# MCU_STM32.net
KiCad netlist of a schematic drawn in Altium Designer
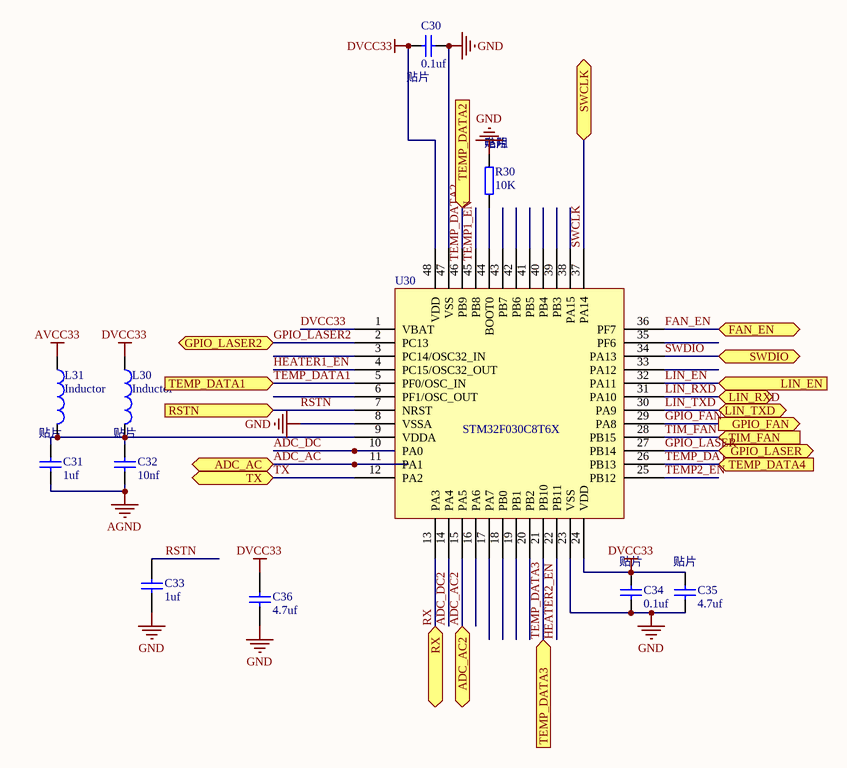
[diagram p0: MCU_STM32.SchDoc]

(export (version "E")
  (design (tool "Eeschema 10.0.6"))
  (components
    (comp (ref "C30")
      (value "0.1uf")
      (footprint "C0402")
      (description "Capacitor (Semiconductor SIM Model)")
      (libsource (lib "Miscellaneous Devices") (part "Cap Semi"))
    )
    (comp (ref "C31")
      (value "1uf")
      (footprint "C0402")
      (description "Capacitor (Semiconductor SIM Model)")
      (libsource (lib "Miscellaneous Devices") (part "Cap Semi"))
    )
    (comp (ref "C32")
      (value "10nf")
      (footprint "C0402")
      (description "Capacitor (Semiconductor SIM Model)")
      (libsource (lib "Miscellaneous Devices") (part "Cap Semi"))
    )
    (comp (ref "C33")
      (value "1uf")
      (footprint "C0402")
      (description "Capacitor 0402")
      (fields (field (name "PUBLISHER") "Altium Limited"))
      (libsource (lib "Capacitors") (part "C0402"))
    )
    (comp (ref "C34")
      (value "0.1uf")
      (footprint "C0402")
      (description "Capacitor (Semiconductor SIM Model)")
      (libsource (lib "Miscellaneous Devices") (part "Cap Semi"))
    )
    (comp (ref "C35")
      (value "4.7uf")
      (footprint "C0402")
      (description "Capacitor (Semiconductor SIM Model)")
      (libsource (lib "Miscellaneous Devices") (part "Cap Semi"))
    )
    (comp (ref "C36")
      (value "4.7uf")
      (footprint "C0402")
      (description "Capacitor 0402")
      (fields (field (name "PUBLISHER") "Altium Limited"))
      (libsource (lib "Capacitors") (part "C0402"))
    )
    (comp (ref "L30")
      (value "Inductor")
      (footprint "L0402")
      (fields (field (name "PUBLISHER") "Altium Limited"))
      (libsource (lib "Miscellaneous Devices") (part "Inductor"))
    )
    (comp (ref "L31")
      (value "Inductor")
      (footprint "L0402")
      (fields (field (name "PUBLISHER") "Altium Limited"))
      (libsource (lib "Miscellaneous Devices") (part "Inductor"))
    )
    (comp (ref "R30") (value "10K") (footprint "R0402") (libsource (lib "CxyDXP_SCH") (part "RES1")))
    (comp (ref "U30")
      (value "STM32F030C8T6X")
      (footprint "LQFP48S")
      (libsource (lib "STM32") (part "STM32F030C8T6X"))
    )
  )
  (nets
    (net (code "1") (name "/ADC_AC") (class "Default")
      (node (ref "U30") (pin "11") (pinfunction "PA1_11") (pintype "passive"))
    )
    (net (code "2") (name "/ADC_AC2") (class "Default")
      (node (ref "U30") (pin "15") (pinfunction "PA5_15") (pintype "passive"))
    )
    (net (code "3") (name "/ADC_DC") (class "Default")
      (node (ref "U30") (pin "10") (pinfunction "PA0_10") (pintype "passive"))
    )
    (net (code "4") (name "/ADC_DC2") (class "Default")
      (node (ref "U30") (pin "14") (pinfunction "PA4_14") (pintype "passive"))
    )
    (net (code "5") (name "/FAN_EN") (class "Default")
      (node (ref "U30") (pin "36") (pinfunction "PF7_36") (pintype "passive"))
    )
    (net (code "6") (name "/GPIO_FAN") (class "Default")
      (node (ref "U30") (pin "29") (pinfunction "PA8_29") (pintype "passive"))
    )
    (net (code "7") (name "/GPIO_LASER") (class "Default")
      (node (ref "U30") (pin "27") (pinfunction "PB14_27") (pintype "passive"))
    )
    (net (code "8") (name "/GPIO_LASER2") (class "Default")
      (node (ref "U30") (pin "2") (pinfunction "PC13_2") (pintype "passive"))
    )
    (net (code "9") (name "/HEATER1_EN") (class "Default")
      (node (ref "U30") (pin "4") (pinfunction "PC15/OSC32_OUT_4") (pintype "passive"))
    )
    (net (code "10") (name "/HEATER2_EN") (class "Default")
      (node (ref "U30") (pin "22") (pinfunction "PB11_22") (pintype "passive"))
    )
    (net (code "11") (name "/LIN_EN") (class "Default")
      (node (ref "U30") (pin "32") (pinfunction "PA11_32") (pintype "passive"))
    )
    (net (code "12") (name "/LIN_RXD") (class "Default")
      (node (ref "U30") (pin "31") (pinfunction "PA10_31") (pintype "passive"))
    )
    (net (code "13") (name "/LIN_TXD") (class "Default")
      (node (ref "U30") (pin "30") (pinfunction "PA9_30") (pintype "passive"))
    )
    (net (code "14") (name "/RSTN") (class "Default")
      (node (ref "C33") (pin "2") (pinfunction "2_2") (pintype "passive"))
      (node (ref "U30") (pin "7") (pinfunction "NRST_7") (pintype "passive"))
    )
    (net (code "15") (name "/RX") (class "Default")
      (node (ref "U30") (pin "13") (pinfunction "PA3_13") (pintype "passive"))
    )
    (net (code "16") (name "/SWCLK") (class "Default")
      (node (ref "U30") (pin "37") (pinfunction "PA14_37") (pintype "passive"))
    )
    (net (code "17") (name "/SWDIO") (class "Default")
      (node (ref "U30") (pin "34") (pinfunction "PA13_34") (pintype "passive"))
    )
    (net (code "19") (name "/TEMP2_EN") (class "Default")
      (node (ref "U30") (pin "25") (pinfunction "PB12_25") (pintype "passive"))
    )
    (net (code "20") (name "/TEMP_DATA1") (class "Default")
      (node (ref "U30") (pin "5") (pinfunction "PF0/OSC_IN_5") (pintype "passive"))
    )
    (net (code "21") (name "/TEMP_DATA2") (class "Default")
      (node (ref "U30") (pin "46") (pinfunction "PB9_46") (pintype "passive"))
    )
    (net (code "22") (name "/TEMP_DATA3") (class "Default")
      (node (ref "U30") (pin "21") (pinfunction "PB10_21") (pintype "passive"))
    )
    (net (code "23") (name "/TEMP_DATA4") (class "Default")
      (node (ref "U30") (pin "26") (pinfunction "PB13_26") (pintype "passive"))
    )
    (net (code "24") (name "/TIM_FAN") (class "Default")
      (node (ref "U30") (pin "28") (pinfunction "PB15_28") (pintype "passive"))
    )
    (net (code "25") (name "/TX") (class "Default")
      (node (ref "U30") (pin "12") (pinfunction "PA2_12") (pintype "passive"))
    )
    (net (code "26") (name "AGND") (class "Default")
      (node (ref "C31") (pin "2") (pinfunction "2_2") (pintype "passive"))
      (node (ref "C32") (pin "2") (pinfunction "2_2") (pintype "passive"))
    )
    (net (code "27") (name "AVCC33") (class "Default")
      (node (ref "L31") (pin "2") (pinfunction "2_2") (pintype "passive"))
    )
    (net (code "28") (name "DVCC33") (class "Default")
      (node (ref "C30") (pin "1") (pinfunction "1_1") (pintype "passive"))
      (node (ref "C34") (pin "1") (pinfunction "1_1") (pintype "passive"))
      (node (ref "C35") (pin "1") (pinfunction "1_1") (pintype "passive"))
      (node (ref "C36") (pin "2") (pinfunction "2_2") (pintype "passive"))
      (node (ref "L30") (pin "2") (pinfunction "2_2") (pintype "passive"))
      (node (ref "U30") (pin "1") (pinfunction "VBAT_1") (pintype "passive"))
      (node (ref "U30") (pin "24") (pinfunction "VDD_24") (pintype "passive"))
      (node (ref "U30") (pin "48") (pinfunction "VDD_48") (pintype "passive"))
    )
    (net (code "29") (name "GND") (class "Default")
      (node (ref "C30") (pin "2") (pinfunction "2_2") (pintype "passive"))
      (node (ref "C33") (pin "1") (pinfunction "1_1") (pintype "passive"))
      (node (ref "C34") (pin "2") (pinfunction "2_2") (pintype "passive"))
      (node (ref "C35") (pin "2") (pinfunction "2_2") (pintype "passive"))
      (node (ref "C36") (pin "1") (pinfunction "1_1") (pintype "passive"))
      (node (ref "R30") (pin "1") (pinfunction "1_1") (pintype "passive"))
      (node (ref "U30") (pin "23") (pinfunction "VSS_23") (pintype "passive"))
      (node (ref "U30") (pin "47") (pinfunction "VSS_47") (pintype "passive"))
      (node (ref "U30") (pin "8") (pinfunction "VSSA_8") (pintype "passive"))
    )
    (net (code "30") (name "Net-(U30-BOOT0)") (class "Default")
      (node (ref "R30") (pin "2") (pinfunction "2_2") (pintype "passive"))
      (node (ref "U30") (pin "44") (pinfunction "BOOT0_44") (pintype "passive"))
    )
    (net (code "31") (name "Net-(U30-VDDA)") (class "Default")
      (node (ref "C31") (pin "1") (pinfunction "1_1") (pintype "passive"))
      (node (ref "C32") (pin "1") (pinfunction "1_1") (pintype "passive"))
      (node (ref "L30") (pin "1") (pinfunction "1_1") (pintype "passive"))
      (node (ref "L31") (pin "1") (pinfunction "1_1") (pintype "passive"))
      (node (ref "U30") (pin "9") (pinfunction "VDDA_9") (pintype "passive"))
    )
    (net (code "32") (name "unconnected-(U30-PA6-Pad16)") (class "Default")
      (node (ref "U30") (pin "16") (pinfunction "PA6_16") (pintype "passive"))
    )
    (net (code "33") (name "unconnected-(U30-PA7-Pad17)") (class "Default")
      (node (ref "U30") (pin "17") (pinfunction "PA7_17") (pintype "passive"))
    )
    (net (code "34") (name "unconnected-(U30-PA12-Pad33)") (class "Default")
      (node (ref "U30") (pin "33") (pinfunction "PA12_33") (pintype "passive"))
    )
    (net (code "35") (name "unconnected-(U30-PA15-Pad38)") (class "Default")
      (node (ref "U30") (pin "38") (pinfunction "PA15_38") (pintype "passive"))
    )
    (net (code "36") (name "unconnected-(U30-PB0-Pad18)") (class "Default")
      (node (ref "U30") (pin "18") (pinfunction "PB0_18") (pintype "passive"))
    )
    (net (code "37") (name "unconnected-(U30-PB1-Pad19)") (class "Default")
      (node (ref "U30") (pin "19") (pinfunction "PB1_19") (pintype "passive"))
    )
    (net (code "38") (name "unconnected-(U30-PB2-Pad20)") (class "Default")
      (node (ref "U30") (pin "20") (pinfunction "PB2_20") (pintype "passive"))
    )
    (net (code "39") (name "unconnected-(U30-PB3-Pad39)") (class "Default")
      (node (ref "U30") (pin "39") (pinfunction "PB3_39") (pintype "passive"))
    )
    (net (code "40") (name "unconnected-(U30-PB4-Pad40)") (class "Default")
      (node (ref "U30") (pin "40") (pinfunction "PB4_40") (pintype "passive"))
    )
    (net (code "41") (name "unconnected-(U30-PB5-Pad41)") (class "Default")
      (node (ref "U30") (pin "41") (pinfunction "PB5_41") (pintype "passive"))
    )
    (net (code "42") (name "unconnected-(U30-PB6-Pad42)") (class "Default")
      (node (ref "U30") (pin "42") (pinfunction "PB6_42") (pintype "passive"))
    )
    (net (code "43") (name "unconnected-(U30-PB7-Pad43)") (class "Default")
      (node (ref "U30") (pin "43") (pinfunction "PB7_43") (pintype "passive"))
    )
    (net (code "44") (name "unconnected-(U30-PB8-Pad45)") (class "Default")
      (node (ref "U30") (pin "45") (pinfunction "PB8_45") (pintype "passive"))
    )
    (net (code "45") (name "unconnected-(U30-PC14{slash}OSC32_IN-Pad3)") (class "Default")
      (node (ref "U30") (pin "3") (pinfunction "PC14/OSC32_IN_3") (pintype "passive"))
    )
    (net (code "46") (name "unconnected-(U30-PF1{slash}OSC_OUT-Pad6)") (class "Default")
      (node (ref "U30") (pin "6") (pinfunction "PF1/OSC_OUT_6") (pintype "passive"))
    )
    (net (code "47") (name "unconnected-(U30-PF6-Pad35)") (class "Default")
      (node (ref "U30") (pin "35") (pinfunction "PF6_35") (pintype "passive"))
    )
  )
)
